# Steering_Wheel_V2_2.net
KiCad netlist of a schematic drawn in EAGLE
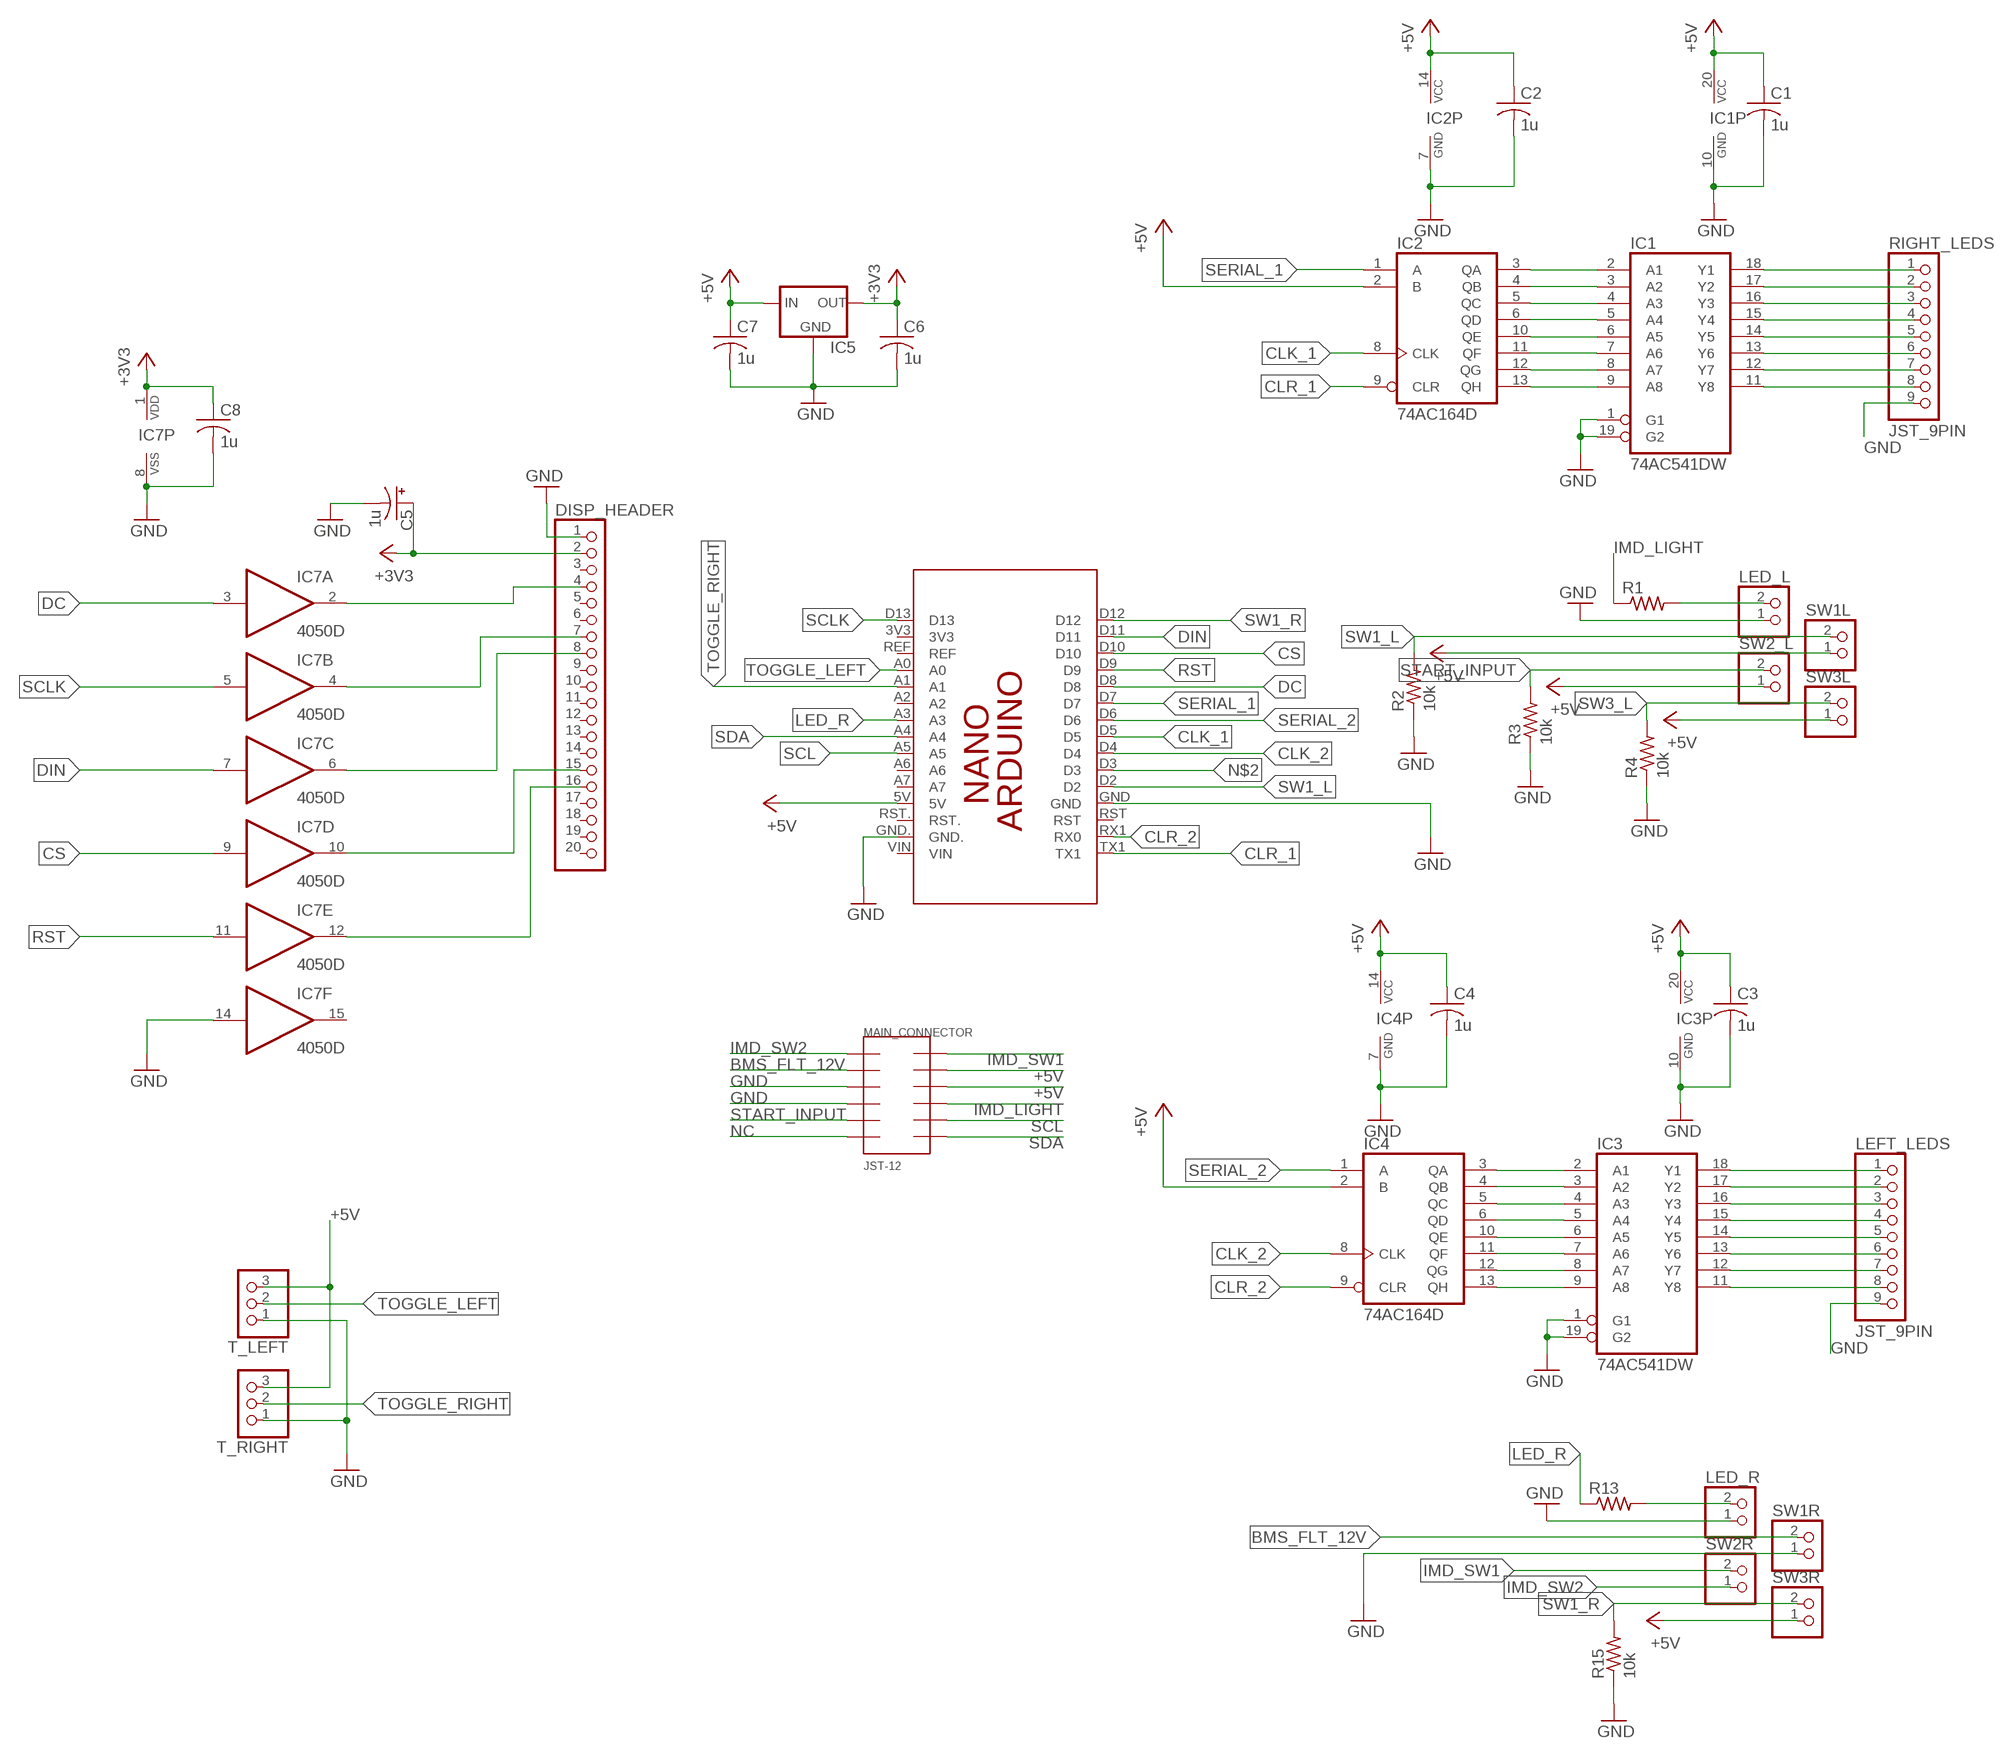
[diagram p0: schematic, sheet 1]

(export (version "E")
  (design (tool "Eeschema 10.0.6"))
  (components
    (comp (ref "C1")
      (value "1u")
      (footprint "eagle-import:C1206")
      (libsource (lib "eagle-import") (part "C-USC1206"))
    )
    (comp (ref "C2")
      (value "1u")
      (footprint "eagle-import:C1206")
      (libsource (lib "eagle-import") (part "C-USC1206"))
    )
    (comp (ref "C3")
      (value "1u")
      (footprint "eagle-import:C1206")
      (libsource (lib "eagle-import") (part "C-USC1206"))
    )
    (comp (ref "C4")
      (value "1u")
      (footprint "eagle-import:C1206")
      (libsource (lib "eagle-import") (part "C-USC1206"))
    )
    (comp (ref "C5")
      (value "1u")
      (footprint "eagle-import:E3,5-8")
      (libsource (lib "eagle-import") (part "CPOL-USE3.5-8"))
    )
    (comp (ref "C6")
      (value "1u")
      (footprint "eagle-import:C1206")
      (libsource (lib "eagle-import") (part "C-USC1206"))
    )
    (comp (ref "C7")
      (value "1u")
      (footprint "eagle-import:C1206")
      (libsource (lib "eagle-import") (part "C-USC1206"))
    )
    (comp (ref "C8")
      (value "1u")
      (footprint "eagle-import:C1206")
      (libsource (lib "eagle-import") (part "C-USC1206"))
    )
    (comp (ref "DISP_HEADER")
      (value "PINHD-1X20")
      (footprint "eagle-import:1X20")
      (libsource (lib "eagle-import") (part "PINHD-1X20"))
    )
    (comp (ref "IC1")
      (value "74AC541DW")
      (footprint "eagle-import:SO20W")
      (libsource (lib "eagle-import") (part "74541DWAC"))
    )
    (comp (ref "IC2")
      (value "74AC164D")
      (footprint "eagle-import:SO14")
      (libsource (lib "eagle-import") (part "74164DAC"))
    )
    (comp (ref "IC3")
      (value "74AC541DW")
      (footprint "eagle-import:SO20W")
      (libsource (lib "eagle-import") (part "74541DWAC"))
    )
    (comp (ref "IC4")
      (value "74AC164D")
      (footprint "eagle-import:SO14")
      (libsource (lib "eagle-import") (part "74164DAC"))
    )
    (comp (ref "IC5")
      (value "78XXL")
      (footprint "eagle-import:78XXL")
      (libsource (lib "eagle-import") (part "78XXL"))
    )
    (comp (ref "IC7")
      (value "4050D")
      (footprint "eagle-import:SO16")
      (libsource (lib "eagle-import") (part "4050D"))
    )
    (comp (ref "LED_L")
      (value "JST_2PIN-THM")
      (footprint "eagle-import:JST-PH-2-THM")
      (libsource (lib "eagle-import") (part "JST_2PIN-THM"))
    )
    (comp (ref "LED_R")
      (value "JST_2PIN-THM")
      (footprint "eagle-import:JST-PH-2-THM")
      (libsource (lib "eagle-import") (part "JST_2PIN-THM"))
    )
    (comp (ref "LEFT_LEDS")
      (value "JST_9PIN")
      (footprint "eagle-import:JST-PH-9-THM")
      (libsource (lib "eagle-import") (part "JST_9PIN"))
    )
    (comp (ref "MAIN_CONNECTOR")
      (value "JST-12")
      (footprint "eagle-import:PHD-12")
      (libsource (lib "eagle-import") (part "JST-12"))
    )
    (comp (ref "PCB1")
      (value "ARDUINO_NANO")
      (footprint "eagle-import:ARDUINO_NANO")
      (libsource (lib "eagle-import") (part "ARDUINO_NANO"))
    )
    (comp (ref "R1")
      (value "R-US_M1206")
      (footprint "eagle-import:M1206")
      (libsource (lib "eagle-import") (part "R-US_M1206"))
    )
    (comp (ref "R2")
      (value "10k")
      (footprint "eagle-import:M1206")
      (libsource (lib "eagle-import") (part "R-US_M1206"))
    )
    (comp (ref "R3")
      (value "10k")
      (footprint "eagle-import:M1206")
      (libsource (lib "eagle-import") (part "R-US_M1206"))
    )
    (comp (ref "R4")
      (value "10k")
      (footprint "eagle-import:M1206")
      (libsource (lib "eagle-import") (part "R-US_M1206"))
    )
    (comp (ref "R13")
      (value "R-US_M1206")
      (footprint "eagle-import:M1206")
      (libsource (lib "eagle-import") (part "R-US_M1206"))
    )
    (comp (ref "R15")
      (value "10k")
      (footprint "eagle-import:M1206")
      (libsource (lib "eagle-import") (part "R-US_M1206"))
    )
    (comp (ref "RIGHT_LEDS")
      (value "JST_9PIN")
      (footprint "eagle-import:JST-PH-9-THM")
      (libsource (lib "eagle-import") (part "JST_9PIN"))
    )
    (comp (ref "SW1L")
      (value "JST_2PIN-THM")
      (footprint "eagle-import:JST-PH-2-THM")
      (libsource (lib "eagle-import") (part "JST_2PIN-THM"))
    )
    (comp (ref "SW1R")
      (value "JST_2PIN-THM")
      (footprint "eagle-import:JST-PH-2-THM")
      (libsource (lib "eagle-import") (part "JST_2PIN-THM"))
    )
    (comp (ref "SW2R")
      (value "JST_2PIN-THM")
      (footprint "eagle-import:JST-PH-2-THM")
      (libsource (lib "eagle-import") (part "JST_2PIN-THM"))
    )
    (comp (ref "SW2_L")
      (value "JST_2PIN-THM")
      (footprint "eagle-import:JST-PH-2-THM")
      (libsource (lib "eagle-import") (part "JST_2PIN-THM"))
    )
    (comp (ref "SW3L")
      (value "JST_2PIN-THM")
      (footprint "eagle-import:JST-PH-2-THM")
      (libsource (lib "eagle-import") (part "JST_2PIN-THM"))
    )
    (comp (ref "SW3R")
      (value "JST_2PIN-THM")
      (footprint "eagle-import:JST-PH-2-THM")
      (libsource (lib "eagle-import") (part "JST_2PIN-THM"))
    )
    (comp (ref "T_LEFT")
      (value "JST_3PIN")
      (footprint "eagle-import:JST-PH-3-THM")
      (libsource (lib "eagle-import") (part "JST_3PIN"))
    )
    (comp (ref "T_RIGHT")
      (value "JST_3PIN")
      (footprint "eagle-import:JST-PH-3-THM")
      (libsource (lib "eagle-import") (part "JST_3PIN"))
    )
  )
  (nets
    (net (code "1") (name "+3V3") (class "Default")
      (node (ref "C5") (pin "+") (pinfunction "+_+") (pintype "passive"))
      (node (ref "C6") (pin "1") (pinfunction "1_1") (pintype "passive"))
      (node (ref "C8") (pin "1") (pinfunction "1_1") (pintype "passive"))
      (node (ref "DISP_HEADER") (pin "2") (pinfunction "2_2") (pintype "passive"))
      (node (ref "IC5") (pin "OUT") (pinfunction "OUT_OUT") (pintype "passive"))
      (node (ref "IC7") (pin "1") (pinfunction "VDD_1") (pintype "power_in"))
    )
    (net (code "2") (name "+5V") (class "Default")
      (node (ref "C1") (pin "1") (pinfunction "1_1") (pintype "passive"))
      (node (ref "C2") (pin "1") (pinfunction "1_1") (pintype "passive"))
      (node (ref "C3") (pin "1") (pinfunction "1_1") (pintype "passive"))
      (node (ref "C4") (pin "1") (pinfunction "1_1") (pintype "passive"))
      (node (ref "C7") (pin "1") (pinfunction "1_1") (pintype "passive"))
      (node (ref "IC1") (pin "20") (pinfunction "VCC_20") (pintype "power_in"))
      (node (ref "IC2") (pin "14") (pinfunction "VCC_14") (pintype "power_in"))
      (node (ref "IC2") (pin "2") (pinfunction "B_2") (pintype "input"))
      (node (ref "IC3") (pin "20") (pinfunction "VCC_20") (pintype "power_in"))
      (node (ref "IC4") (pin "14") (pinfunction "VCC_14") (pintype "power_in"))
      (node (ref "IC4") (pin "2") (pinfunction "B_2") (pintype "input"))
      (node (ref "IC5") (pin "IN") (pinfunction "IN_IN") (pintype "input"))
      (node (ref "MAIN_CONNECTOR") (pin "10") (pinfunction "10_10") (pintype "bidirectional"))
      (node (ref "MAIN_CONNECTOR") (pin "11") (pinfunction "11_11") (pintype "bidirectional"))
      (node (ref "PCB1") (pin "5V") (pinfunction "5V_5V") (pintype "bidirectional"))
      (node (ref "SW1L") (pin "1") (pinfunction "2_1") (pintype "passive"))
      (node (ref "SW2_L") (pin "1") (pinfunction "2_1") (pintype "passive"))
      (node (ref "SW3L") (pin "1") (pinfunction "2_1") (pintype "passive"))
      (node (ref "SW3R") (pin "1") (pinfunction "2_1") (pintype "passive"))
      (node (ref "T_LEFT") (pin "3") (pinfunction "3_3") (pintype "passive"))
      (node (ref "T_RIGHT") (pin "3") (pinfunction "3_3") (pintype "passive"))
    )
    (net (code "3") (name "/IMD_LIGHT") (class "Default")
      (node (ref "MAIN_CONNECTOR") (pin "9") (pinfunction "9_9") (pintype "bidirectional"))
      (node (ref "R1") (pin "1") (pinfunction "1_1") (pintype "passive"))
    )
    (net (code "4") (name "/NC") (class "Default")
      (node (ref "MAIN_CONNECTOR") (pin "6") (pinfunction "6_6") (pintype "bidirectional"))
    )
    (net (code "5") (name "BMS_FLT_12V") (class "Default")
      (node (ref "MAIN_CONNECTOR") (pin "2") (pinfunction "2_2") (pintype "bidirectional"))
      (node (ref "SW1R") (pin "2") (pinfunction "1_2") (pintype "passive"))
    )
    (net (code "6") (name "CLK_1") (class "Default")
      (node (ref "IC2") (pin "8") (pinfunction "CLK_8") (pintype "input"))
      (node (ref "PCB1") (pin "D5") (pinfunction "D5_D5") (pintype "bidirectional"))
    )
    (net (code "7") (name "CLK_2") (class "Default")
      (node (ref "IC4") (pin "8") (pinfunction "CLK_8") (pintype "input"))
      (node (ref "PCB1") (pin "D4") (pinfunction "D4_D4") (pintype "bidirectional"))
    )
    (net (code "8") (name "CLR_1") (class "Default")
      (node (ref "IC2") (pin "9") (pinfunction "CLR_9") (pintype "input"))
      (node (ref "PCB1") (pin "TX1") (pinfunction "TX1_TX1") (pintype "bidirectional"))
    )
    (net (code "9") (name "CLR_2") (class "Default")
      (node (ref "IC4") (pin "9") (pinfunction "CLR_9") (pintype "input"))
      (node (ref "PCB1") (pin "RX1") (pinfunction "RX0_RX1") (pintype "bidirectional"))
    )
    (net (code "10") (name "CS") (class "Default")
      (node (ref "IC7") (pin "9") (pinfunction "I_9") (pintype "input"))
      (node (ref "PCB1") (pin "D10") (pinfunction "D10_D10") (pintype "bidirectional"))
    )
    (net (code "11") (name "DC") (class "Default")
      (node (ref "IC7") (pin "3") (pinfunction "I_3") (pintype "input"))
      (node (ref "PCB1") (pin "D8") (pinfunction "D8_D8") (pintype "bidirectional"))
    )
    (net (code "12") (name "DIN") (class "Default")
      (node (ref "IC7") (pin "7") (pinfunction "I_7") (pintype "input"))
      (node (ref "PCB1") (pin "D11") (pinfunction "D11_D11") (pintype "bidirectional"))
    )
    (net (code "13") (name "GND") (class "Default")
      (node (ref "C1") (pin "2") (pinfunction "2_2") (pintype "passive"))
      (node (ref "C2") (pin "2") (pinfunction "2_2") (pintype "passive"))
      (node (ref "C3") (pin "2") (pinfunction "2_2") (pintype "passive"))
      (node (ref "C4") (pin "2") (pinfunction "2_2") (pintype "passive"))
      (node (ref "C5") (pin "-") (pinfunction "-_-") (pintype "passive"))
      (node (ref "C6") (pin "2") (pinfunction "2_2") (pintype "passive"))
      (node (ref "C7") (pin "2") (pinfunction "2_2") (pintype "passive"))
      (node (ref "C8") (pin "2") (pinfunction "2_2") (pintype "passive"))
      (node (ref "DISP_HEADER") (pin "1") (pinfunction "1_1") (pintype "passive"))
      (node (ref "IC1") (pin "1") (pinfunction "G1_1") (pintype "input"))
      (node (ref "IC1") (pin "10") (pinfunction "GND_10") (pintype "power_in"))
      (node (ref "IC1") (pin "19") (pinfunction "G2_19") (pintype "input"))
      (node (ref "IC2") (pin "7") (pinfunction "GND_7") (pintype "power_in"))
      (node (ref "IC3") (pin "1") (pinfunction "G1_1") (pintype "input"))
      (node (ref "IC3") (pin "10") (pinfunction "GND_10") (pintype "power_in"))
      (node (ref "IC3") (pin "19") (pinfunction "G2_19") (pintype "input"))
      (node (ref "IC4") (pin "7") (pinfunction "GND_7") (pintype "power_in"))
      (node (ref "IC5") (pin "GND") (pinfunction "GND_GND") (pintype "input"))
      (node (ref "IC7") (pin "14") (pinfunction "I_14") (pintype "input"))
      (node (ref "IC7") (pin "8") (pinfunction "VSS_8") (pintype "power_in"))
      (node (ref "LED_L") (pin "1") (pinfunction "2_1") (pintype "passive"))
      (node (ref "LED_R") (pin "1") (pinfunction "2_1") (pintype "passive"))
      (node (ref "LEFT_LEDS") (pin "9") (pinfunction "9_9") (pintype "passive"))
      (node (ref "MAIN_CONNECTOR") (pin "3") (pinfunction "3_3") (pintype "bidirectional"))
      (node (ref "MAIN_CONNECTOR") (pin "4") (pinfunction "4_4") (pintype "bidirectional"))
      (node (ref "PCB1") (pin "GND") (pinfunction "GND_GND") (pintype "bidirectional"))
      (node (ref "PCB1") (pin "GND.") (pinfunction "GND._GND.") (pintype "bidirectional"))
      (node (ref "R15") (pin "1") (pinfunction "1_1") (pintype "passive"))
      (node (ref "R2") (pin "1") (pinfunction "1_1") (pintype "passive"))
      (node (ref "R3") (pin "1") (pinfunction "1_1") (pintype "passive"))
      (node (ref "R4") (pin "1") (pinfunction "1_1") (pintype "passive"))
      (node (ref "RIGHT_LEDS") (pin "9") (pinfunction "9_9") (pintype "passive"))
      (node (ref "SW1R") (pin "1") (pinfunction "2_1") (pintype "passive"))
      (node (ref "T_LEFT") (pin "1") (pinfunction "1_1") (pintype "passive"))
      (node (ref "T_RIGHT") (pin "1") (pinfunction "1_1") (pintype "passive"))
    )
    (net (code "14") (name "IMD_SW1") (class "Default")
      (node (ref "MAIN_CONNECTOR") (pin "12") (pinfunction "12_12") (pintype "bidirectional"))
      (node (ref "SW2R") (pin "2") (pinfunction "1_2") (pintype "passive"))
    )
    (net (code "15") (name "IMD_SW2") (class "Default")
      (node (ref "MAIN_CONNECTOR") (pin "1") (pinfunction "1_1") (pintype "bidirectional"))
      (node (ref "SW2R") (pin "1") (pinfunction "2_1") (pintype "passive"))
    )
    (net (code "16") (name "LED_R") (class "Default")
      (node (ref "PCB1") (pin "A3") (pinfunction "A3_A3") (pintype "bidirectional"))
      (node (ref "R13") (pin "1") (pinfunction "1_1") (pintype "passive"))
    )
    (net (code "17") (name "N$2") (class "Default")
      (node (ref "PCB1") (pin "D3") (pinfunction "D3_D3") (pintype "bidirectional"))
    )
    (net (code "18") (name "Net-(IC1A-A1)") (class "Default")
      (node (ref "IC1") (pin "2") (pinfunction "A1_2") (pintype "input"))
      (node (ref "IC2") (pin "3") (pinfunction "QA_3") (pintype "output"))
    )
    (net (code "19") (name "Net-(IC1A-A2)") (class "Default")
      (node (ref "IC1") (pin "3") (pinfunction "A2_3") (pintype "input"))
      (node (ref "IC2") (pin "4") (pinfunction "QB_4") (pintype "output"))
    )
    (net (code "20") (name "Net-(IC1A-A3)") (class "Default")
      (node (ref "IC1") (pin "4") (pinfunction "A3_4") (pintype "input"))
      (node (ref "IC2") (pin "5") (pinfunction "QC_5") (pintype "output"))
    )
    (net (code "21") (name "Net-(IC1A-A4)") (class "Default")
      (node (ref "IC1") (pin "5") (pinfunction "A4_5") (pintype "input"))
      (node (ref "IC2") (pin "6") (pinfunction "QD_6") (pintype "output"))
    )
    (net (code "22") (name "Net-(IC1A-A5)") (class "Default")
      (node (ref "IC1") (pin "6") (pinfunction "A5_6") (pintype "input"))
      (node (ref "IC2") (pin "10") (pinfunction "QE_10") (pintype "output"))
    )
    (net (code "23") (name "Net-(IC1A-A6)") (class "Default")
      (node (ref "IC1") (pin "7") (pinfunction "A6_7") (pintype "input"))
      (node (ref "IC2") (pin "11") (pinfunction "QF_11") (pintype "output"))
    )
    (net (code "24") (name "Net-(IC1A-A7)") (class "Default")
      (node (ref "IC1") (pin "8") (pinfunction "A7_8") (pintype "input"))
      (node (ref "IC2") (pin "12") (pinfunction "QG_12") (pintype "output"))
    )
    (net (code "25") (name "Net-(IC1A-A8)") (class "Default")
      (node (ref "IC1") (pin "9") (pinfunction "A8_9") (pintype "input"))
      (node (ref "IC2") (pin "13") (pinfunction "QH_13") (pintype "output"))
    )
    (net (code "26") (name "Net-(IC1A-Y1)") (class "Default")
      (node (ref "IC1") (pin "18") (pinfunction "Y1_18") (pintype "tri_state"))
      (node (ref "RIGHT_LEDS") (pin "1") (pinfunction "1_1") (pintype "passive"))
    )
    (net (code "27") (name "Net-(IC1A-Y2)") (class "Default")
      (node (ref "IC1") (pin "17") (pinfunction "Y2_17") (pintype "tri_state"))
      (node (ref "RIGHT_LEDS") (pin "2") (pinfunction "2_2") (pintype "passive"))
    )
    (net (code "28") (name "Net-(IC1A-Y3)") (class "Default")
      (node (ref "IC1") (pin "16") (pinfunction "Y3_16") (pintype "tri_state"))
      (node (ref "RIGHT_LEDS") (pin "3") (pinfunction "3_3") (pintype "passive"))
    )
    (net (code "29") (name "Net-(IC1A-Y4)") (class "Default")
      (node (ref "IC1") (pin "15") (pinfunction "Y4_15") (pintype "tri_state"))
      (node (ref "RIGHT_LEDS") (pin "4") (pinfunction "4_4") (pintype "passive"))
    )
    (net (code "30") (name "Net-(IC1A-Y5)") (class "Default")
      (node (ref "IC1") (pin "14") (pinfunction "Y5_14") (pintype "tri_state"))
      (node (ref "RIGHT_LEDS") (pin "5") (pinfunction "5_5") (pintype "passive"))
    )
    (net (code "31") (name "Net-(IC1A-Y6)") (class "Default")
      (node (ref "IC1") (pin "13") (pinfunction "Y6_13") (pintype "tri_state"))
      (node (ref "RIGHT_LEDS") (pin "6") (pinfunction "6_6") (pintype "passive"))
    )
    (net (code "32") (name "Net-(IC1A-Y7)") (class "Default")
      (node (ref "IC1") (pin "12") (pinfunction "Y7_12") (pintype "tri_state"))
      (node (ref "RIGHT_LEDS") (pin "7") (pinfunction "7_7") (pintype "passive"))
    )
    (net (code "33") (name "Net-(IC1A-Y8)") (class "Default")
      (node (ref "IC1") (pin "11") (pinfunction "Y8_11") (pintype "tri_state"))
      (node (ref "RIGHT_LEDS") (pin "8") (pinfunction "8_8") (pintype "passive"))
    )
    (net (code "34") (name "Net-(IC3A-A1)") (class "Default")
      (node (ref "IC3") (pin "2") (pinfunction "A1_2") (pintype "input"))
      (node (ref "IC4") (pin "3") (pinfunction "QA_3") (pintype "output"))
    )
    (net (code "35") (name "Net-(IC3A-A2)") (class "Default")
      (node (ref "IC3") (pin "3") (pinfunction "A2_3") (pintype "input"))
      (node (ref "IC4") (pin "4") (pinfunction "QB_4") (pintype "output"))
    )
    (net (code "36") (name "Net-(IC3A-A3)") (class "Default")
      (node (ref "IC3") (pin "4") (pinfunction "A3_4") (pintype "input"))
      (node (ref "IC4") (pin "5") (pinfunction "QC_5") (pintype "output"))
    )
    (net (code "37") (name "Net-(IC3A-A4)") (class "Default")
      (node (ref "IC3") (pin "5") (pinfunction "A4_5") (pintype "input"))
      (node (ref "IC4") (pin "6") (pinfunction "QD_6") (pintype "output"))
    )
    (net (code "38") (name "Net-(IC3A-A5)") (class "Default")
      (node (ref "IC3") (pin "6") (pinfunction "A5_6") (pintype "input"))
      (node (ref "IC4") (pin "10") (pinfunction "QE_10") (pintype "output"))
    )
    (net (code "39") (name "Net-(IC3A-A6)") (class "Default")
      (node (ref "IC3") (pin "7") (pinfunction "A6_7") (pintype "input"))
      (node (ref "IC4") (pin "11") (pinfunction "QF_11") (pintype "output"))
    )
    (net (code "40") (name "Net-(IC3A-A7)") (class "Default")
      (node (ref "IC3") (pin "8") (pinfunction "A7_8") (pintype "input"))
      (node (ref "IC4") (pin "12") (pinfunction "QG_12") (pintype "output"))
    )
    (net (code "41") (name "Net-(IC3A-A8)") (class "Default")
      (node (ref "IC3") (pin "9") (pinfunction "A8_9") (pintype "input"))
      (node (ref "IC4") (pin "13") (pinfunction "QH_13") (pintype "output"))
    )
    (net (code "42") (name "Net-(IC3A-Y1)") (class "Default")
      (node (ref "IC3") (pin "18") (pinfunction "Y1_18") (pintype "tri_state"))
      (node (ref "LEFT_LEDS") (pin "1") (pinfunction "1_1") (pintype "passive"))
    )
    (net (code "43") (name "Net-(IC3A-Y2)") (class "Default")
      (node (ref "IC3") (pin "17") (pinfunction "Y2_17") (pintype "tri_state"))
      (node (ref "LEFT_LEDS") (pin "2") (pinfunction "2_2") (pintype "passive"))
    )
    (net (code "44") (name "Net-(IC3A-Y3)") (class "Default")
      (node (ref "IC3") (pin "16") (pinfunction "Y3_16") (pintype "tri_state"))
      (node (ref "LEFT_LEDS") (pin "3") (pinfunction "3_3") (pintype "passive"))
    )
    (net (code "45") (name "Net-(IC3A-Y4)") (class "Default")
      (node (ref "IC3") (pin "15") (pinfunction "Y4_15") (pintype "tri_state"))
      (node (ref "LEFT_LEDS") (pin "4") (pinfunction "4_4") (pintype "passive"))
    )
    (net (code "46") (name "Net-(IC3A-Y5)") (class "Default")
      (node (ref "IC3") (pin "14") (pinfunction "Y5_14") (pintype "tri_state"))
      (node (ref "LEFT_LEDS") (pin "5") (pinfunction "5_5") (pintype "passive"))
    )
    (net (code "47") (name "Net-(IC3A-Y6)") (class "Default")
      (node (ref "IC3") (pin "13") (pinfunction "Y6_13") (pintype "tri_state"))
      (node (ref "LEFT_LEDS") (pin "6") (pinfunction "6_6") (pintype "passive"))
    )
    (net (code "48") (name "Net-(IC3A-Y7)") (class "Default")
      (node (ref "IC3") (pin "12") (pinfunction "Y7_12") (pintype "tri_state"))
      (node (ref "LEFT_LEDS") (pin "7") (pinfunction "7_7") (pintype "passive"))
    )
    (net (code "49") (name "Net-(IC3A-Y8)") (class "Default")
      (node (ref "IC3") (pin "11") (pinfunction "Y8_11") (pintype "tri_state"))
      (node (ref "LEFT_LEDS") (pin "8") (pinfunction "8_8") (pintype "passive"))
    )
    (net (code "50") (name "Net-(IC7A-O)") (class "Default")
      (node (ref "DISP_HEADER") (pin "4") (pinfunction "4_4") (pintype "passive"))
      (node (ref "IC7") (pin "2") (pinfunction "O_2") (pintype "output"))
    )
    (net (code "51") (name "Net-(IC7B-O)") (class "Default")
      (node (ref "DISP_HEADER") (pin "7") (pinfunction "7_7") (pintype "passive"))
      (node (ref "IC7") (pin "4") (pinfunction "O_4") (pintype "output"))
    )
    (net (code "52") (name "Net-(IC7C-O)") (class "Default")
      (node (ref "DISP_HEADER") (pin "8") (pinfunction "8_8") (pintype "passive"))
      (node (ref "IC7") (pin "6") (pinfunction "O_6") (pintype "output"))
    )
    (net (code "53") (name "Net-(IC7D-O)") (class "Default")
      (node (ref "DISP_HEADER") (pin "15") (pinfunction "15_15") (pintype "passive"))
      (node (ref "IC7") (pin "10") (pinfunction "O_10") (pintype "output"))
    )
    (net (code "54") (name "Net-(IC7E-O)") (class "Default")
      (node (ref "DISP_HEADER") (pin "16") (pinfunction "16_16") (pintype "passive"))
      (node (ref "IC7") (pin "12") (pinfunction "O_12") (pintype "output"))
    )
    (net (code "55") (name "Net-(LED_L-1)") (class "Default")
      (node (ref "LED_L") (pin "2") (pinfunction "1_2") (pintype "passive"))
      (node (ref "R1") (pin "2") (pinfunction "2_2") (pintype "passive"))
    )
    (net (code "56") (name "Net-(LED_R-1)") (class "Default")
      (node (ref "LED_R") (pin "2") (pinfunction "1_2") (pintype "passive"))
      (node (ref "R13") (pin "2") (pinfunction "2_2") (pintype "passive"))
    )
    (net (code "57") (name "RST") (class "Default")
      (node (ref "IC7") (pin "11") (pinfunction "I_11") (pintype "input"))
      (node (ref "PCB1") (pin "D9") (pinfunction "D9_D9") (pintype "bidirectional"))
    )
    (net (code "58") (name "SCL") (class "Default")
      (node (ref "MAIN_CONNECTOR") (pin "8") (pinfunction "8_8") (pintype "bidirectional"))
      (node (ref "PCB1") (pin "A5") (pinfunction "A5_A5") (pintype "bidirectional"))
    )
    (net (code "59") (name "SCLK") (class "Default")
      (node (ref "IC7") (pin "5") (pinfunction "I_5") (pintype "input"))
      (node (ref "PCB1") (pin "D13") (pinfunction "D13_D13") (pintype "bidirectional"))
    )
    (net (code "60") (name "SDA") (class "Default")
      (node (ref "MAIN_CONNECTOR") (pin "7") (pinfunction "7_7") (pintype "bidirectional"))
      (node (ref "PCB1") (pin "A4") (pinfunction "A4_A4") (pintype "bidirectional"))
    )
    (net (code "61") (name "SERIAL_1") (class "Default")
      (node (ref "IC2") (pin "1") (pinfunction "A_1") (pintype "input"))
      (node (ref "PCB1") (pin "D7") (pinfunction "D7_D7") (pintype "bidirectional"))
    )
    (net (code "62") (name "SERIAL_2") (class "Default")
      (node (ref "IC4") (pin "1") (pinfunction "A_1") (pintype "input"))
      (node (ref "PCB1") (pin "D6") (pinfunction "D6_D6") (pintype "bidirectional"))
    )
    (net (code "63") (name "START_INPUT") (class "Default")
      (node (ref "MAIN_CONNECTOR") (pin "5") (pinfunction "5_5") (pintype "bidirectional"))
      (node (ref "R3") (pin "2") (pinfunction "2_2") (pintype "passive"))
      (node (ref "SW2_L") (pin "2") (pinfunction "1_2") (pintype "passive"))
    )
    (net (code "64") (name "SW1_L") (class "Default")
      (node (ref "PCB1") (pin "D2") (pinfunction "D2_D2") (pintype "bidirectional"))
      (node (ref "R2") (pin "2") (pinfunction "2_2") (pintype "passive"))
      (node (ref "SW1L") (pin "2") (pinfunction "1_2") (pintype "passive"))
    )
    (net (code "65") (name "SW1_R") (class "Default")
      (node (ref "PCB1") (pin "D12") (pinfunction "D12_D12") (pintype "bidirectional"))
      (node (ref "R15") (pin "2") (pinfunction "2_2") (pintype "passive"))
      (node (ref "SW3R") (pin "2") (pinfunction "1_2") (pintype "passive"))
    )
    (net (code "66") (name "SW3_L") (class "Default")
      (node (ref "R4") (pin "2") (pinfunction "2_2") (pintype "passive"))
      (node (ref "SW3L") (pin "2") (pinfunction "1_2") (pintype "passive"))
    )
    (net (code "67") (name "TOGGLE_LEFT") (class "Default")
      (node (ref "PCB1") (pin "A0") (pinfunction "A0_A0") (pintype "bidirectional"))
      (node (ref "T_LEFT") (pin "2") (pinfunction "2_2") (pintype "passive"))
    )
    (net (code "68") (name "TOGGLE_RIGHT") (class "Default")
      (node (ref "PCB1") (pin "A1") (pinfunction "A1_A1") (pintype "bidirectional"))
      (node (ref "T_RIGHT") (pin "2") (pinfunction "2_2") (pintype "passive"))
    )
    (net (code "69") (name "unconnected-(DISP_HEADER-Pad3)") (class "Default")
      (node (ref "DISP_HEADER") (pin "3") (pinfunction "3_3") (pintype "passive"))
    )
    (net (code "70") (name "unconnected-(DISP_HEADER-Pad5)") (class "Default")
      (node (ref "DISP_HEADER") (pin "5") (pinfunction "5_5") (pintype "passive"))
    )
    (net (code "71") (name "unconnected-(DISP_HEADER-Pad6)") (class "Default")
      (node (ref "DISP_HEADER") (pin "6") (pinfunction "6_6") (pintype "passive"))
    )
    (net (code "72") (name "unconnected-(DISP_HEADER-Pad9)") (class "Default")
      (node (ref "DISP_HEADER") (pin "9") (pinfunction "9_9") (pintype "passive"))
    )
    (net (code "73") (name "unconnected-(DISP_HEADER-Pad10)") (class "Default")
      (node (ref "DISP_HEADER") (pin "10") (pinfunction "10_10") (pintype "passive"))
    )
    (net (code "74") (name "unconnected-(DISP_HEADER-Pad11)") (class "Default")
      (node (ref "DISP_HEADER") (pin "11") (pinfunction "11_11") (pintype "passive"))
    )
    (net (code "75") (name "unconnected-(DISP_HEADER-Pad12)") (class "Default")
      (node (ref "DISP_HEADER") (pin "12") (pinfunction "12_12") (pintype "passive"))
    )
    (net (code "76") (name "unconnected-(DISP_HEADER-Pad13)") (class "Default")
      (node (ref "DISP_HEADER") (pin "13") (pinfunction "13_13") (pintype "passive"))
    )
    (net (code "77") (name "unconnected-(DISP_HEADER-Pad14)") (class "Default")
      (node (ref "DISP_HEADER") (pin "14") (pinfunction "14_14") (pintype "passive"))
    )
    (net (code "78") (name "unconnected-(DISP_HEADER-Pad17)") (class "Default")
      (node (ref "DISP_HEADER") (pin "17") (pinfunction "17_17") (pintype "passive"))
    )
    (net (code "79") (name "unconnected-(DISP_HEADER-Pad18)") (class "Default")
      (node (ref "DISP_HEADER") (pin "18") (pinfunction "18_18") (pintype "passive"))
    )
    (net (code "80") (name "unconnected-(DISP_HEADER-Pad19)") (class "Default")
      (node (ref "DISP_HEADER") (pin "19") (pinfunction "19_19") (pintype "passive"))
    )
    (net (code "81") (name "unconnected-(DISP_HEADER-Pad20)") (class "Default")
      (node (ref "DISP_HEADER") (pin "20") (pinfunction "20_20") (pintype "passive"))
    )
    (net (code "82") (name "unconnected-(IC7F-O-Pad15)") (class "Default")
      (node (ref "IC7") (pin "15") (pinfunction "O_15") (pintype "output"))
    )
    (net (code "83") (name "unconnected-(PCB1-Pad3V3)") (class "Default")
      (node (ref "PCB1") (pin "3V3") (pinfunction "3V3_3V3") (pintype "bidirectional"))
    )
    (net (code "84") (name "unconnected-(PCB1-PadA2)") (class "Default")
      (node (ref "PCB1") (pin "A2") (pinfunction "A2_A2") (pintype "bidirectional"))
    )
    (net (code "85") (name "unconnected-(PCB1-PadA6)") (class "Default")
      (node (ref "PCB1") (pin "A6") (pinfunction "A6_A6") (pintype "bidirectional"))
    )
    (net (code "86") (name "unconnected-(PCB1-PadA7)") (class "Default")
      (node (ref "PCB1") (pin "A7") (pinfunction "A7_A7") (pintype "bidirectional"))
    )
    (net (code "87") (name "unconnected-(PCB1-PadREF)") (class "Default")
      (node (ref "PCB1") (pin "REF") (pinfunction "REF_REF") (pintype "bidirectional"))
    )
    (net (code "88") (name "unconnected-(PCB1-PadRST)") (class "Default")
      (node (ref "PCB1") (pin "RST") (pinfunction "RST_RST") (pintype "bidirectional"))
    )
    (net (code "89") (name "unconnected-(PCB1-PadRST.)") (class "Default")
      (node (ref "PCB1") (pin "RST.") (pinfunction "RST._RST.") (pintype "bidirectional"))
    )
    (net (code "90") (name "unconnected-(PCB1-PadVIN)") (class "Default")
      (node (ref "PCB1") (pin "VIN") (pinfunction "VIN_VIN") (pintype "bidirectional"))
    )
  )
)
